# Audio.net
KiCad netlist of a schematic drawn in Altium Designer
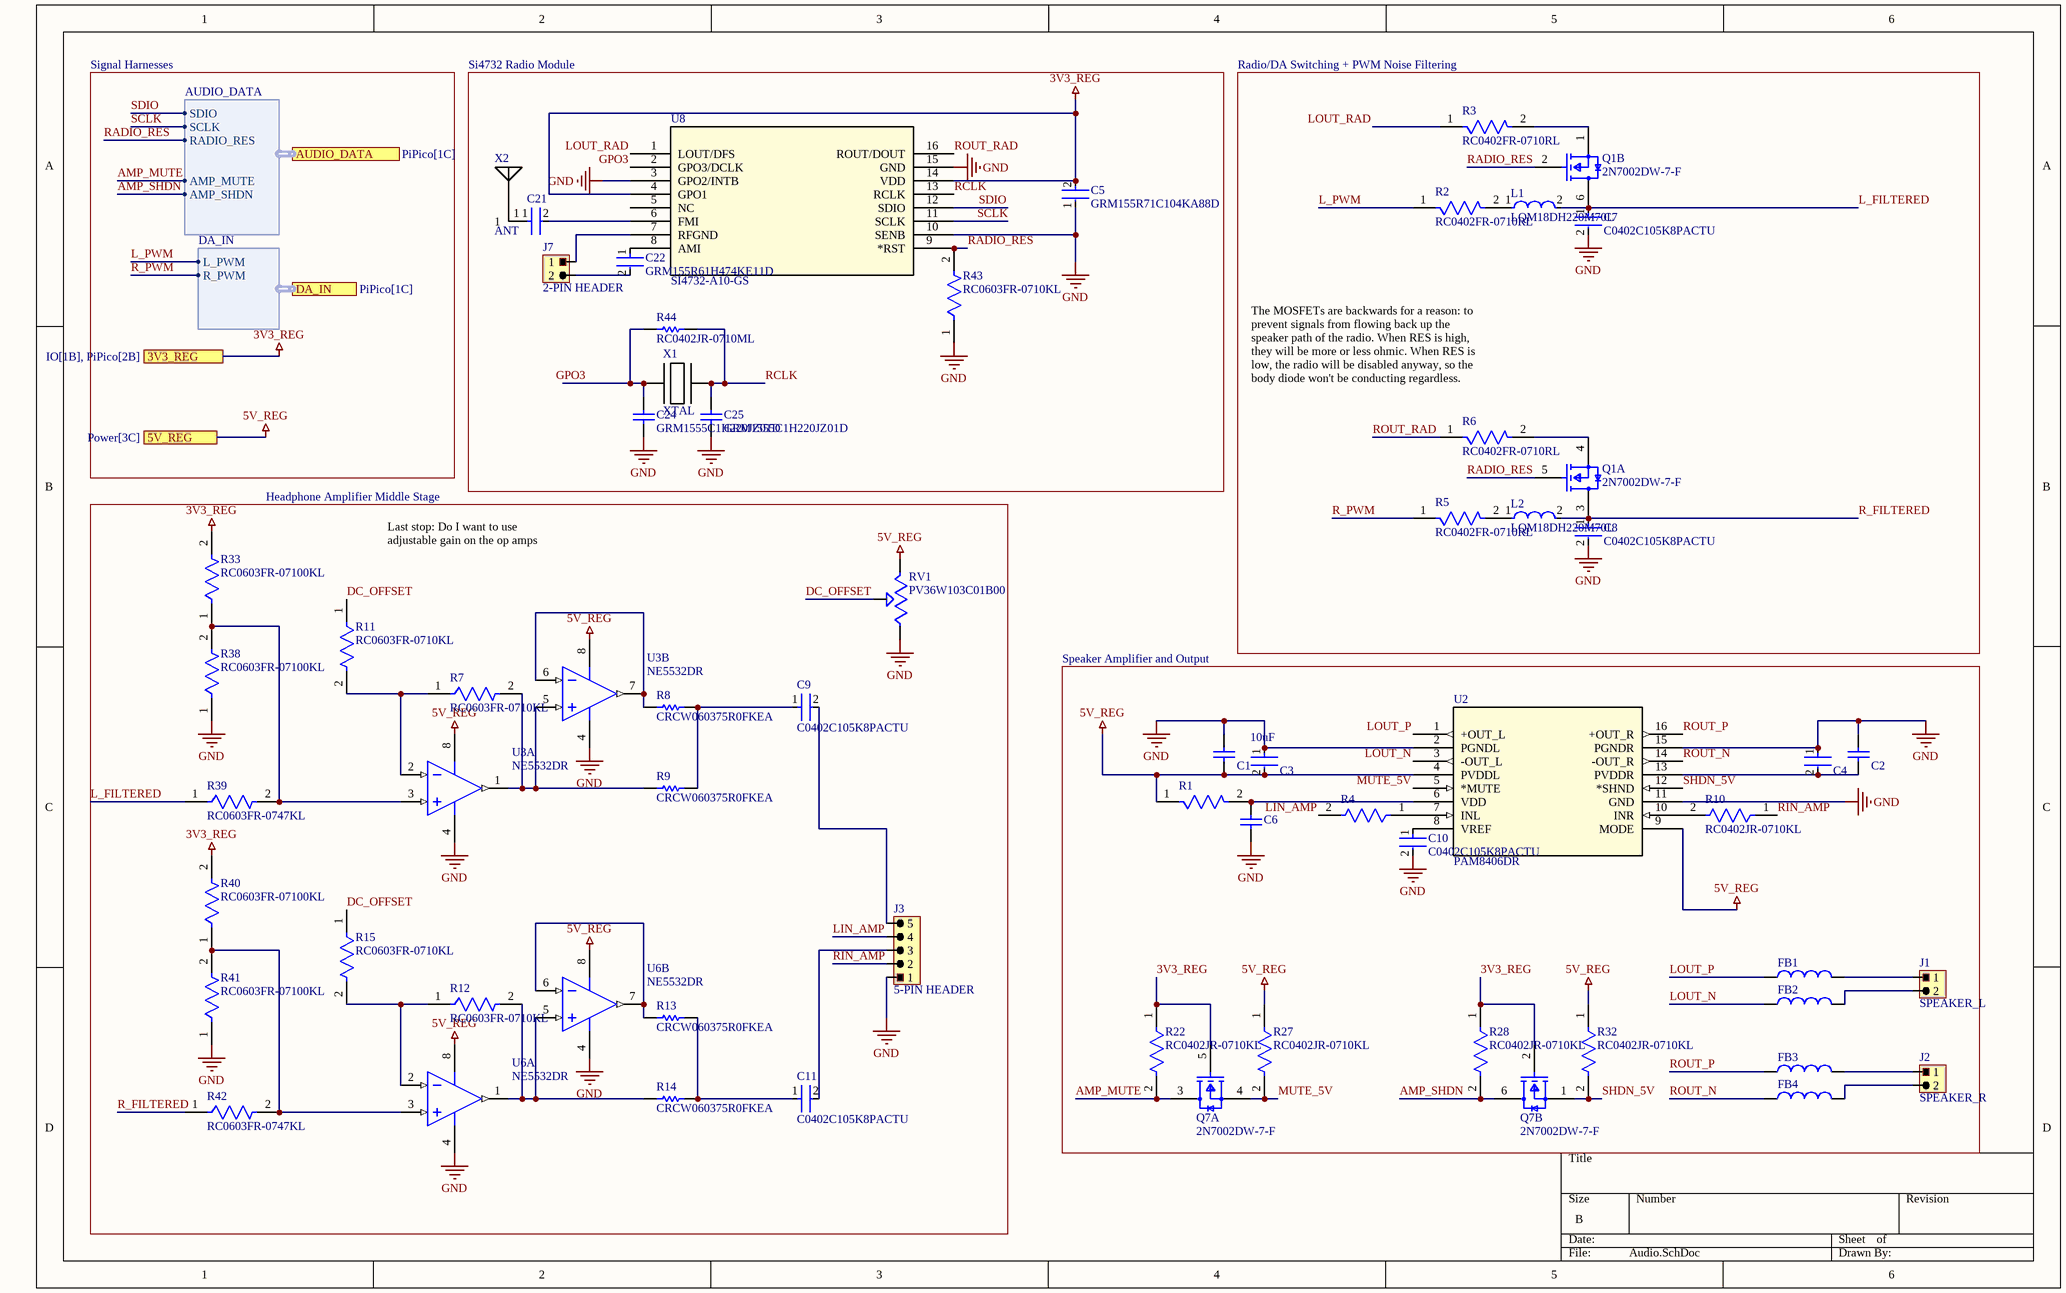
[diagram p0: Audio.SchDoc]

(export (version "E")
  (design (tool "Eeschema 10.0.6"))
  (components
    (comp (ref "C1")
      (value "C0603C105K3RACTU")
      (footprint "CAPC1608X87X35LL15T15")
      (fields (field (name "MANUFACTURER") "Kemet"))
      (libsource (lib "Altium Content Vault") (part "CAP"))
    )
    (comp (ref "C2")
      (value "C0603C105K3RACTU")
      (footprint "CAPC1608X87X35LL15T15")
      (fields (field (name "MANUFACTURER") "Kemet"))
      (libsource (lib "Altium Content Vault") (part "CAP"))
    )
    (comp (ref "C3")
      (value "C0805C106K8PACTU")
      (footprint "FP-C0805C-DG-MFG")
      (description "CAP CER 10UF 10V X5R 0805")
      (fields
        (field (name "TOLERANCE") "10%")
        (field (name "MANUFACTURER") "Kemet")
        (field (name "CAPACITANCE") "10uF")
      )
      (libsource (lib "Altium Content Vault") (part "11868f565c42a9108669ba33697ecf6"))
    )
    (comp (ref "C4")
      (value "C0805C106K8PACTU")
      (footprint "FP-C0805C-DG-MFG")
      (description "CAP CER 10UF 10V X5R 0805")
      (fields (field (name "TOLERANCE") "10%") (field (name "MANUFACTURER") "Kemet"))
      (libsource (lib "Altium Content Vault") (part "11868f565c42a9108669ba33697ecf6"))
    )
    (comp (ref "C5")
      (value "GRM155R71C104KA88D")
      (footprint "FP-GRM15-MFG")
      (description "CAP CER 0.1UF 16V X7R 0402")
      (fields
        (field (name "TOLERANCE") "10%")
        (field (name "OCTOPART") "https://octopart.com/grm155r71c104ka88d-murata-196880")
      )
      (libsource (lib "Altium Content Vault") (part "236180d848d6139a670b325ea6854c9"))
    )
    (comp (ref "C6")
      (value "C0603C105K3RACTU")
      (footprint "CAPC1608X87X35LL15T15")
      (fields (field (name "MANUFACTURER") "Kemet"))
      (libsource (lib "Altium Content Vault") (part "CAP"))
    )
    (comp (ref "C7")
      (value "C0402C105K8PACTU")
      (footprint "FP-C0402C105K8PACTU-MFG")
      (description "CAP CER 1UF 10V X5R 0402")
      (fields (field (name "VOLTAGE") "10V") (field (name "TOLERANCE") "10%"))
      (libsource (lib "Altium Content Vault") (part "11868f565c42a9108669ba33697ecf6"))
    )
    (comp (ref "C8")
      (value "C0402C105K8PACTU")
      (footprint "FP-C0402C105K8PACTU-MFG")
      (description "CAP CER 1UF 10V X5R 0402")
      (fields (field (name "VOLTAGE") "10V") (field (name "TOLERANCE") "10%"))
      (libsource (lib "Altium Content Vault") (part "11868f565c42a9108669ba33697ecf6"))
    )
    (comp (ref "C9")
      (value "C0402C105K8PACTU")
      (footprint "FP-C0402C105K8PACTU-MFG")
      (description "CAP CER 1UF 10V X5R 0402")
      (fields (field (name "VOLTAGE") "10V") (field (name "TOLERANCE") "10%"))
      (libsource (lib "Altium Content Vault") (part "11868f565c42a9108669ba33697ecf6"))
    )
    (comp (ref "C10")
      (value "C0402C105K8PACTU")
      (footprint "FP-C0402C105K8PACTU-MFG")
      (description "CAP CER 1UF 10V X5R 0402")
      (fields (field (name "VOLTAGE") "10V") (field (name "TOLERANCE") "10%"))
      (libsource (lib "Altium Content Vault") (part "11868f565c42a9108669ba33697ecf6"))
    )
    (comp (ref "C11")
      (value "C0402C105K8PACTU")
      (footprint "FP-C0402C105K8PACTU-MFG")
      (description "CAP CER 1UF 10V X5R 0402")
      (fields (field (name "VOLTAGE") "10V") (field (name "TOLERANCE") "10%"))
      (libsource (lib "Altium Content Vault") (part "11868f565c42a9108669ba33697ecf6"))
    )
    (comp (ref "C21")
      (value "GRM1555C1H102JA01D")
      (footprint "FP-GRM155-0_05-IPC_B")
      (description "Chip Multilayer Ceramic Capacitors for General Purpose, 0402, 1000pF, C0G, 30ppm/°C, 5%, 50V")
      (fields (field (name "TOLERANCE") "5%") (field (name "VOLTAGE") "50V"))
      (libsource (lib "Altium Content Vault") (part "02cd4be3c70576c341d710602a673aa"))
    )
    (comp (ref "C22")
      (value "GRM155R61H474KE11D")
      (footprint "FP-GRM155-0_1-IPC_B")
      (description "Chip Multilayer Ceramic Capacitors for General Purpose, 0402, 0.47uF, X5R, 15%, 10%, 50V")
      (fields (field (name "TOLERANCE") "10%"))
      (libsource (lib "Altium Content Vault") (part "11868f565c42a9108669ba33697ecf6"))
    )
    (comp (ref "C24")
      (value "GRM1555C1H220JZ01D")
      (footprint "CAPC1005X55X25NL05T10")
      (fields (field (name "MANUFACTURER") "Murata"))
      (libsource (lib "Altium Content Vault") (part "CAP"))
    )
    (comp (ref "C25")
      (value "GRM1555C1H220JZ01D")
      (footprint "CAPC1005X55X25NL05T10")
      (fields (field (name "MANUFACTURER") "Murata"))
      (libsource (lib "Altium Content Vault") (part "CAP"))
    )
    (comp (ref "FB1")
      (value "742792097")
      (footprint "WE-CBF_0805_L2W1.2H0.9_HC")
      (fields (field (name "TOLERANCE") "25%"))
      (libsource (lib "Altium Content Vault") (part "Ferrite"))
    )
    (comp (ref "FB2")
      (value "742792097")
      (footprint "WE-CBF_0805_L2W1.2H0.9_HC")
      (fields (field (name "TOLERANCE") "25%"))
      (libsource (lib "Altium Content Vault") (part "Ferrite"))
    )
    (comp (ref "FB3")
      (value "742792097")
      (footprint "WE-CBF_0805_L2W1.2H0.9_HC")
      (fields (field (name "TOLERANCE") "25%"))
      (libsource (lib "Altium Content Vault") (part "Ferrite"))
    )
    (comp (ref "FB4")
      (value "742792097")
      (footprint "WE-CBF_0805_L2W1.2H0.9_HC")
      (fields (field (name "TOLERANCE") "25%"))
      (libsource (lib "Altium Content Vault") (part "Ferrite"))
    )
    (comp (ref "J1")
      (value "SPEAKER_L")
      (footprint "2-pin Header (Generic)")
      (libsource (lib "") (part "2-PIN HEADER_1"))
    )
    (comp (ref "J2")
      (value "SPEAKER_R")
      (footprint "2-pin Header (Generic)")
      (libsource (lib "") (part "2-PIN HEADER_1"))
    )
    (comp (ref "J3")
      (value "5-PIN HEADER")
      (footprint "5-pin Header (Generic)")
      (libsource (lib "ECE299_PCB") (part "5-PIN HEADER"))
    )
    (comp (ref "J7")
      (value "2-PIN HEADER")
      (footprint "2-pin Header (Generic)")
      (libsource (lib "ECE299_PCB") (part "2-PIN HEADER"))
    )
    (comp (ref "L1")
      (value "LQM18DH220M70L")
      (footprint "FP-LQM18DN_70-MFG")
      (description "LQM18DH220M70L Inductor Chip Shielded Multilayer 22uH 20% 1MHz Ferrite 200mA 0603 Emboss T/R")
      (fields (field (name "TOLERANCE") "20%"))
      (libsource (lib "Altium Content Vault") (part "725321dda6339637d4d059423bc1c3c"))
    )
    (comp (ref "L2")
      (value "LQM18DH220M70L")
      (footprint "FP-LQM18DN_70-MFG")
      (description "LQM18DH220M70L Inductor Chip Shielded Multilayer 22uH 20% 1MHz Ferrite 200mA 0603 Emboss T/R")
      (fields (field (name "TOLERANCE") "20%"))
      (libsource (lib "Altium Content Vault") (part "725321dda6339637d4d059423bc1c3c"))
    )
    (comp (ref "Q1")
      (value "2N7002DW-7-F")
      (footprint "FP-SOT363-IPC_C")
      (description "MOSFET 2N-CH 60V 0.23A SOT-363")
      (libsource (lib "Altium Content Vault") (part "ecafc9d1340cdd65b0d02313e96d8fb"))
    )
    (comp (ref "Q7")
      (value "2N7002DW-7-F")
      (footprint "FP-SOT363-IPC_C")
      (description "MOSFET 2N-CH 60V 0.23A SOT-363")
      (libsource (lib "Altium Content Vault") (part "ecafc9d1340cdd65b0d02313e96d8fb"))
    )
    (comp (ref "R1")
      (value "RC0402FR-0710RL")
      (footprint "FP-RC0402-0_4-MFG")
      (fields (field (name "TOLERANCE") "1%"))
      (libsource (lib "Altium Content Vault") (part "1029c3af85768c4190bb7ad29bc67b5"))
    )
    (comp (ref "R2")
      (value "RC0402FR-0710RL")
      (footprint "FP-RC0402-0_4-MFG")
      (fields (field (name "TOLERANCE") "1%"))
      (libsource (lib "Altium Content Vault") (part "1029c3af85768c4190bb7ad29bc67b5"))
    )
    (comp (ref "R3")
      (value "RC0402FR-0710RL")
      (footprint "FP-RC0402-0_4-MFG")
      (fields (field (name "TOLERANCE") "1%"))
      (libsource (lib "Altium Content Vault") (part "1029c3af85768c4190bb7ad29bc67b5"))
    )
    (comp (ref "R4")
      (value "RC0402JR-0710KL")
      (footprint "RC0402N_YAG")
      (description "RES 10K OHM 5% 1/16W 0402")
      (fields (field (name "TOLERANCE") "5%"))
      (libsource (lib "ECE299_PCB") (part "CMP-2002-07915-3"))
    )
    (comp (ref "R5")
      (value "RC0402FR-0710RL")
      (footprint "FP-RC0402-0_4-MFG")
      (fields (field (name "TOLERANCE") "1%"))
      (libsource (lib "Altium Content Vault") (part "1029c3af85768c4190bb7ad29bc67b5"))
    )
    (comp (ref "R6")
      (value "RC0402FR-0710RL")
      (footprint "FP-RC0402-0_4-MFG")
      (fields (field (name "TOLERANCE") "1%"))
      (libsource (lib "Altium Content Vault") (part "1029c3af85768c4190bb7ad29bc67b5"))
    )
    (comp (ref "R7")
      (value "RC0603FR-0710KL")
      (footprint "FP-RC0603-0_55-IPC_C")
      (description "RES 10K OHM 1% 1/10W 0603")
      (fields (field (name "TOLERANCE") "1%"))
      (libsource (lib "Altium Content Vault") (part "1029c3af85768c4190bb7ad29bc67b5"))
    )
    (comp (ref "R8")
      (value "CRCW060375R0FKEA")
      (footprint "RESC1609X50X30LL10T20")
      (fields (field (name "MANUFACTURER") "Vishay Dale"))
      (libsource (lib "Altium Content Vault") (part "RES"))
    )
    (comp (ref "R9")
      (value "CRCW060375R0FKEA")
      (footprint "RESC1609X50X30LL10T20")
      (fields (field (name "MANUFACTURER") "Vishay Dale"))
      (libsource (lib "Altium Content Vault") (part "RES"))
    )
    (comp (ref "R10")
      (value "RC0402JR-0710KL")
      (footprint "RC0402N_YAG")
      (description "RES 10K OHM 5% 1/16W 0402")
      (fields (field (name "TOLERANCE") "5%"))
      (libsource (lib "ECE299_PCB") (part "CMP-2002-07915-3"))
    )
    (comp (ref "R11")
      (value "RC0603FR-0710KL")
      (footprint "FP-RC0603-0_55-IPC_C")
      (description "RES 10K OHM 1% 1/10W 0603")
      (fields (field (name "TOLERANCE") "1%"))
      (libsource (lib "Altium Content Vault") (part "1029c3af85768c4190bb7ad29bc67b5"))
    )
    (comp (ref "R12")
      (value "RC0603FR-0710KL")
      (footprint "FP-RC0603-0_55-IPC_C")
      (description "RES 10K OHM 1% 1/10W 0603")
      (fields (field (name "TOLERANCE") "1%"))
      (libsource (lib "Altium Content Vault") (part "1029c3af85768c4190bb7ad29bc67b5"))
    )
    (comp (ref "R13")
      (value "CRCW060375R0FKEA")
      (footprint "RESC1609X50X30LL10T20")
      (fields (field (name "MANUFACTURER") "Vishay Dale"))
      (libsource (lib "Altium Content Vault") (part "RES"))
    )
    (comp (ref "R14")
      (value "CRCW060375R0FKEA")
      (footprint "RESC1609X50X30LL10T20")
      (fields (field (name "MANUFACTURER") "Vishay Dale"))
      (libsource (lib "Altium Content Vault") (part "RES"))
    )
    (comp (ref "R15")
      (value "RC0603FR-0710KL")
      (footprint "FP-RC0603-0_55-IPC_C")
      (description "RES 10K OHM 1% 1/10W 0603")
      (fields (field (name "TOLERANCE") "1%"))
      (libsource (lib "Altium Content Vault") (part "1029c3af85768c4190bb7ad29bc67b5"))
    )
    (comp (ref "R22")
      (value "RC0402JR-0710KL")
      (footprint "RC0402N_YAG")
      (description "RES 10K OHM 5% 1/16W 0402")
      (fields (field (name "TOLERANCE") "5%"))
      (libsource (lib "ECE299_PCB") (part "CMP-2002-07915-3"))
    )
    (comp (ref "R27")
      (value "RC0402JR-0710KL")
      (footprint "RC0402N_YAG")
      (description "RES 10K OHM 5% 1/16W 0402")
      (fields (field (name "TOLERANCE") "5%"))
      (libsource (lib "ECE299_PCB") (part "CMP-2002-07915-3"))
    )
    (comp (ref "R28")
      (value "RC0402JR-0710KL")
      (footprint "RC0402N_YAG")
      (description "RES 10K OHM 5% 1/16W 0402")
      (fields (field (name "TOLERANCE") "5%"))
      (libsource (lib "ECE299_PCB") (part "CMP-2002-07915-3"))
    )
    (comp (ref "R32")
      (value "RC0402JR-0710KL")
      (footprint "RC0402N_YAG")
      (description "RES 10K OHM 5% 1/16W 0402")
      (fields (field (name "TOLERANCE") "5%"))
      (libsource (lib "ECE299_PCB") (part "CMP-2002-07915-3"))
    )
    (comp (ref "R33")
      (value "RC0603FR-07100KL")
      (footprint "FP-RC0603-0_55-MFG")
      (description "RES SMD 100K OHM 1% 1/10W 0603")
      (fields (field (name "TOLERANCE") "1%"))
      (libsource (lib "Altium Content Vault") (part "1029c3af85768c4190bb7ad29bc67b5"))
    )
    (comp (ref "R38")
      (value "RC0603FR-07100KL")
      (footprint "FP-RC0603-0_55-MFG")
      (description "RES SMD 100K OHM 1% 1/10W 0603")
      (fields (field (name "TOLERANCE") "1%"))
      (libsource (lib "Altium Content Vault") (part "1029c3af85768c4190bb7ad29bc67b5"))
    )
    (comp (ref "R39")
      (value "RC0603FR-0747KL")
      (footprint "FP-RC0603FR-0747KL-MFG")
      (description "RES SMD 47K OHM 1% 1/10W 0603")
      (fields (field (name "TOLERANCE") "1%"))
      (libsource (lib "Altium Content Vault") (part "1029c3af85768c4190bb7ad29bc67b5"))
    )
    (comp (ref "R40")
      (value "RC0603FR-07100KL")
      (footprint "FP-RC0603-0_55-MFG")
      (description "RES SMD 100K OHM 1% 1/10W 0603")
      (fields (field (name "TOLERANCE") "1%"))
      (libsource (lib "Altium Content Vault") (part "1029c3af85768c4190bb7ad29bc67b5"))
    )
    (comp (ref "R41")
      (value "RC0603FR-07100KL")
      (footprint "FP-RC0603-0_55-MFG")
      (description "RES SMD 100K OHM 1% 1/10W 0603")
      (fields (field (name "TOLERANCE") "1%"))
      (libsource (lib "Altium Content Vault") (part "1029c3af85768c4190bb7ad29bc67b5"))
    )
    (comp (ref "R42")
      (value "RC0603FR-0747KL")
      (footprint "FP-RC0603FR-0747KL-MFG")
      (description "RES SMD 47K OHM 1% 1/10W 0603")
      (fields (field (name "TOLERANCE") "1%"))
      (libsource (lib "Altium Content Vault") (part "1029c3af85768c4190bb7ad29bc67b5"))
    )
    (comp (ref "R43")
      (value "RC0603FR-0710KL")
      (footprint "FP-RC0603-0_55-IPC_C")
      (description "RES 10K OHM 1% 1/10W 0603")
      (fields (field (name "TOLERANCE") "1%"))
      (libsource (lib "Altium Content Vault") (part "1029c3af85768c4190bb7ad29bc67b5"))
    )
    (comp (ref "R44")
      (value "RC0402JR-0710ML")
      (footprint "RESC1005X40X25ML05T10")
      (fields (field (name "MANUFACTURER") "Yageo / Phycomp"))
      (libsource (lib "Altium Content Vault") (part "RES"))
    )
    (comp (ref "RV1")
      (value "PV36W103C01B00")
      (footprint "TRIM_PV36W103C01B00")
      (description "10 kOhms 0.5W, 1/2W PC Pins Through Hole Trimmer Potentiometer Cermet 25.0 Turn Top Adjustment")
      (fields (field (name "DIGIKEY_PART_NUMBER") "118-PV36W103C01B00-ND") (field (name "MF") "Bourns"))
      (libsource (lib "ECE299_PCB") (part "PV36W103C01B00"))
    )
    (comp (ref "U2")
      (value "PAM8406DR")
      (footprint "SO-16_PAM8406_DIO")
      (description "No Description Available")
      (libsource (lib "ECE299_PCB") (part "PAM8406DR"))
    )
    (comp (ref "U3")
      (value "NE5532DR")
      (footprint "D0008A_N")
      (fields (field (name "MANUFACTURER") "Texas Instruments"))
      (libsource (lib "Altium Content Vault") (part "TI-AMP-D6-2-8_D"))
    )
    (comp (ref "U6")
      (value "NE5532DR")
      (footprint "D0008A_N")
      (fields (field (name "MANUFACTURER") "Texas Instruments"))
      (libsource (lib "Altium Content Vault") (part "TI-AMP-D6-2-8_D"))
    )
    (comp (ref "U8")
      (value "SI4732-A10-GS")
      (footprint "SOIC_A10-GS_SIL")
      (description "No Description Available")
      (libsource (lib "ECE299_PCB") (part "SI4732-A10-GS"))
    )
    (comp (ref "X1")
      (value "XTAL")
      (footprint "FC-135 32.7680KA-AG0")
      (libsource (lib "ECE299_PCB") (part "FC-135 32.7680KA-AG0"))
    )
    (comp (ref "X2")
      (value "ANT")
      (footprint "FM_ANTENNA_OUT")
      (libsource (lib "ECE299_PCB") (part "FM_OUT"))
    )
  )
  (nets
    (net (code "3") (name "/AMP_MUTE") (class "Default")
      (node (ref "Q7") (pin "3") (pinfunction "D1_3") (pintype "passive"))
      (node (ref "R22") (pin "2") (pinfunction "2_2") (pintype "passive"))
    )
    (net (code "4") (name "/AMP_SHDN") (class "Default")
      (node (ref "Q7") (pin "6") (pinfunction "D2_6") (pintype "passive"))
      (node (ref "R28") (pin "2") (pinfunction "2_2") (pintype "passive"))
    )
    (net (code "5") (name "/DC_OFFSET") (class "Default")
      (node (ref "R11") (pin "1") (pinfunction "1_1") (pintype "passive"))
      (node (ref "R15") (pin "1") (pinfunction "1_1") (pintype "passive"))
      (node (ref "RV1") (pin "2") (pinfunction "2_2") (pintype "passive"))
    )
    (net (code "6") (name "/GPO3") (class "Default")
      (node (ref "C24") (pin "2") (pinfunction "2_2") (pintype "passive"))
      (node (ref "R44") (pin "1") (pinfunction "1_1") (pintype "passive"))
      (node (ref "U8") (pin "2") (pinfunction "GPO3/DCLK_2") (pintype "passive"))
      (node (ref "X1") (pin "2") (pinfunction "2_2") (pintype "passive"))
    )
    (net (code "7") (name "/LIN_AMP") (class "Default")
      (node (ref "J3") (pin "4") (pinfunction "4_4") (pintype "passive"))
      (node (ref "R4") (pin "2") (pinfunction "2_2") (pintype "passive"))
    )
    (net (code "8") (name "/LOUT_N") (class "Default")
      (node (ref "FB2") (pin "1") (pinfunction "1_1") (pintype "passive"))
      (node (ref "U2") (pin "3") (pinfunction "-OUT_L_3") (pintype "output"))
    )
    (net (code "9") (name "/LOUT_P") (class "Default")
      (node (ref "FB1") (pin "1") (pinfunction "1_1") (pintype "passive"))
      (node (ref "U2") (pin "1") (pinfunction "+OUT_L_1") (pintype "output"))
    )
    (net (code "10") (name "/LOUT_RAD") (class "Default")
      (node (ref "R3") (pin "1") (pinfunction "1_1") (pintype "passive"))
      (node (ref "U8") (pin "1") (pinfunction "LOUT/DFS_1") (pintype "passive"))
    )
    (net (code "11") (name "/L_FILTERED") (class "Default")
      (node (ref "C7") (pin "1") (pinfunction "1_1") (pintype "passive"))
      (node (ref "L1") (pin "2") (pinfunction "2_2") (pintype "passive"))
      (node (ref "Q1") (pin "6") (pinfunction "D2_6") (pintype "passive"))
      (node (ref "R39") (pin "1") (pinfunction "1_1") (pintype "passive"))
    )
    (net (code "12") (name "/L_PWM") (class "Default")
      (node (ref "R2") (pin "1") (pinfunction "1_1") (pintype "passive"))
    )
    (net (code "13") (name "/MUTE_5V") (class "Default")
      (node (ref "Q7") (pin "4") (pinfunction "S1_4") (pintype "passive"))
      (node (ref "R27") (pin "2") (pinfunction "2_2") (pintype "passive"))
      (node (ref "U2") (pin "5") (pinfunction "*MUTE_5") (pintype "input"))
    )
    (net (code "14") (name "/RADIO_RES") (class "Default")
      (node (ref "Q1") (pin "2") (pinfunction "G2_2") (pintype "passive"))
      (node (ref "Q1") (pin "5") (pinfunction "G1_5") (pintype "passive"))
      (node (ref "R43") (pin "2") (pinfunction "2_2") (pintype "passive"))
      (node (ref "U8") (pin "9") (pinfunction "*RST_9") (pintype "passive"))
    )
    (net (code "15") (name "/RCLK") (class "Default")
      (node (ref "C25") (pin "2") (pinfunction "2_2") (pintype "passive"))
      (node (ref "R44") (pin "2") (pinfunction "2_2") (pintype "passive"))
      (node (ref "U8") (pin "13") (pinfunction "RCLK_13") (pintype "passive"))
      (node (ref "X1") (pin "1") (pinfunction "1_1") (pintype "passive"))
    )
    (net (code "16") (name "/RIN_AMP") (class "Default")
      (node (ref "J3") (pin "2") (pinfunction "2_2") (pintype "passive"))
      (node (ref "R10") (pin "1") (pinfunction "1_1") (pintype "passive"))
    )
    (net (code "17") (name "/ROUT_N") (class "Default")
      (node (ref "FB4") (pin "1") (pinfunction "1_1") (pintype "passive"))
      (node (ref "U2") (pin "14") (pinfunction "-OUT_R_14") (pintype "output"))
    )
    (net (code "18") (name "/ROUT_P") (class "Default")
      (node (ref "FB3") (pin "1") (pinfunction "1_1") (pintype "passive"))
      (node (ref "U2") (pin "16") (pinfunction "+OUT_R_16") (pintype "output"))
    )
    (net (code "19") (name "/ROUT_RAD") (class "Default")
      (node (ref "R6") (pin "1") (pinfunction "1_1") (pintype "passive"))
      (node (ref "U8") (pin "16") (pinfunction "ROUT/DOUT_16") (pintype "passive"))
    )
    (net (code "20") (name "/R_FILTERED") (class "Default")
      (node (ref "C8") (pin "1") (pinfunction "1_1") (pintype "passive"))
      (node (ref "L2") (pin "2") (pinfunction "2_2") (pintype "passive"))
      (node (ref "Q1") (pin "3") (pinfunction "D1_3") (pintype "passive"))
      (node (ref "R42") (pin "1") (pinfunction "1_1") (pintype "passive"))
    )
    (net (code "21") (name "/R_PWM") (class "Default")
      (node (ref "R5") (pin "1") (pinfunction "1_1") (pintype "passive"))
    )
    (net (code "22") (name "/SCLK") (class "Default")
      (node (ref "U8") (pin "11") (pinfunction "SCLK_11") (pintype "passive"))
    )
    (net (code "23") (name "/SDIO") (class "Default")
      (node (ref "U8") (pin "12") (pinfunction "SDIO_12") (pintype "passive"))
    )
    (net (code "24") (name "/SHDN_5V") (class "Default")
      (node (ref "Q7") (pin "1") (pinfunction "S2_1") (pintype "passive"))
      (node (ref "R32") (pin "2") (pinfunction "2_2") (pintype "passive"))
      (node (ref "U2") (pin "12") (pinfunction "*SHND_12") (pintype "input"))
    )
    (net (code "27") (name "3V3_REG") (class "Default")
      (node (ref "C5") (pin "2") (pinfunction "2_2") (pintype "passive"))
      (node (ref "Q7") (pin "2") (pinfunction "G2_2") (pintype "passive"))
      (node (ref "Q7") (pin "5") (pinfunction "G1_5") (pintype "passive"))
      (node (ref "R22") (pin "1") (pinfunction "1_1") (pintype "passive"))
      (node (ref "R28") (pin "1") (pinfunction "1_1") (pintype "passive"))
      (node (ref "R33") (pin "2") (pinfunction "2_2") (pintype "passive"))
      (node (ref "R40") (pin "2") (pinfunction "2_2") (pintype "passive"))
      (node (ref "U8") (pin "14") (pinfunction "VDD_14") (pintype "power_in"))
      (node (ref "U8") (pin "4") (pinfunction "GPO1_4") (pintype "passive"))
    )
    (net (code "28") (name "5V_REG") (class "Default")
      (node (ref "C1") (pin "1") (pinfunction "1_1") (pintype "passive"))
      (node (ref "C3") (pin "2") (pinfunction "2_2") (pintype "passive"))
      (node (ref "R1") (pin "1") (pinfunction "1_1") (pintype "passive"))
      (node (ref "R27") (pin "1") (pinfunction "1_1") (pintype "passive"))
      (node (ref "R32") (pin "1") (pinfunction "1_1") (pintype "passive"))
      (node (ref "RV1") (pin "3") (pinfunction "3_3") (pintype "passive"))
      (node (ref "U2") (pin "4") (pinfunction "PVDDL_4") (pintype "power_in"))
      (node (ref "U2") (pin "9") (pinfunction "MODE_9") (pintype "passive"))
      (node (ref "U3") (pin "8") (pinfunction "VCC+_8") (pintype "power_in"))
      (node (ref "U6") (pin "8") (pinfunction "VCC+_8") (pintype "power_in"))
    )
    (net (code "29") (name "GND") (class "Default")
      (node (ref "C1") (pin "2") (pinfunction "2_2") (pintype "passive"))
      (node (ref "C10") (pin "2") (pinfunction "2_2") (pintype "passive"))
      (node (ref "C2") (pin "2") (pinfunction "2_2") (pintype "passive"))
      (node (ref "C24") (pin "1") (pinfunction "1_1") (pintype "passive"))
      (node (ref "C25") (pin "1") (pinfunction "1_1") (pintype "passive"))
      (node (ref "C3") (pin "1") (pinfunction "1_1") (pintype "passive"))
      (node (ref "C4") (pin "1") (pinfunction "1_1") (pintype "passive"))
      (node (ref "C5") (pin "1") (pinfunction "1_1") (pintype "passive"))
      (node (ref "C6") (pin "1") (pinfunction "1_1") (pintype "passive"))
      (node (ref "C7") (pin "2") (pinfunction "2_2") (pintype "passive"))
      (node (ref "C8") (pin "2") (pinfunction "2_2") (pintype "passive"))
      (node (ref "J3") (pin "1") (pinfunction "1_1") (pintype "passive"))
      (node (ref "R38") (pin "1") (pinfunction "1_1") (pintype "passive"))
      (node (ref "R41") (pin "1") (pinfunction "1_1") (pintype "passive"))
      (node (ref "R43") (pin "1") (pinfunction "1_1") (pintype "passive"))
      (node (ref "RV1") (pin "1") (pinfunction "1_1") (pintype "passive"))
      (node (ref "U2") (pin "11") (pinfunction "GND_11") (pintype "power_in"))
      (node (ref "U2") (pin "15") (pinfunction "PGNDR_15") (pintype "power_in"))
      (node (ref "U2") (pin "2") (pinfunction "PGNDL_2") (pintype "power_in"))
      (node (ref "U3") (pin "4") (pinfunction "VCC-_4") (pintype "power_in"))
      (node (ref "U6") (pin "4") (pinfunction "VCC-_4") (pintype "power_in"))
      (node (ref "U8") (pin "10") (pinfunction "SENB_10") (pintype "passive"))
      (node (ref "U8") (pin "15") (pinfunction "GND_15") (pintype "power_in"))
      (node (ref "U8") (pin "3") (pinfunction "GPO2/INTB_3") (pintype "passive"))
    )
    (net (code "30") (name "Net-(C9-Pad1)") (class "Default")
      (node (ref "C9") (pin "1") (pinfunction "1_1") (pintype "passive"))
      (node (ref "R8") (pin "2") (pinfunction "2_2") (pintype "passive"))
      (node (ref "R9") (pin "2") (pinfunction "2_2") (pintype "passive"))
    )
    (net (code "31") (name "Net-(C9-Pad2)") (class "Default")
      (node (ref "C9") (pin "2") (pinfunction "2_2") (pintype "passive"))
      (node (ref "J3") (pin "5") (pinfunction "5_5") (pintype "passive"))
    )
    (net (code "32") (name "Net-(C11-Pad1)") (class "Default")
      (node (ref "C11") (pin "1") (pinfunction "1_1") (pintype "passive"))
      (node (ref "R13") (pin "2") (pinfunction "2_2") (pintype "passive"))
      (node (ref "R14") (pin "2") (pinfunction "2_2") (pintype "passive"))
    )
    (net (code "33") (name "Net-(C11-Pad2)") (class "Default")
      (node (ref "C11") (pin "2") (pinfunction "2_2") (pintype "passive"))
      (node (ref "J3") (pin "3") (pinfunction "3_3") (pintype "passive"))
    )
    (net (code "34") (name "Net-(C21-Pad1)") (class "Default")
      (node (ref "C21") (pin "1") (pinfunction "1_1") (pintype "passive"))
      (node (ref "X2") (pin "1") (pinfunction "1_1") (pintype "passive"))
    )
    (net (code "35") (name "Net-(C22-Pad2)") (class "Default")
      (node (ref "C22") (pin "2") (pinfunction "2_2") (pintype "passive"))
      (node (ref "J7") (pin "2") (pinfunction "2_2") (pintype "passive"))
    )
    (net (code "36") (name "Net-(FB1-Pad2)") (class "Default")
      (node (ref "FB1") (pin "2") (pinfunction "2_2") (pintype "passive"))
      (node (ref "J1") (pin "1") (pinfunction "1_1") (pintype "passive"))
    )
    (net (code "37") (name "Net-(FB2-Pad2)") (class "Default")
      (node (ref "FB2") (pin "2") (pinfunction "2_2") (pintype "passive"))
      (node (ref "J1") (pin "2") (pinfunction "2_2") (pintype "passive"))
    )
    (net (code "38") (name "Net-(FB3-Pad2)") (class "Default")
      (node (ref "FB3") (pin "2") (pinfunction "2_2") (pintype "passive"))
      (node (ref "J2") (pin "1") (pinfunction "1_1") (pintype "passive"))
    )
    (net (code "39") (name "Net-(FB4-Pad2)") (class "Default")
      (node (ref "FB4") (pin "2") (pinfunction "2_2") (pintype "passive"))
      (node (ref "J2") (pin "2") (pinfunction "2_2") (pintype "passive"))
    )
    (net (code "40") (name "Net-(L1-Pad1)") (class "Default")
      (node (ref "L1") (pin "1") (pinfunction "1_1") (pintype "passive"))
      (node (ref "R2") (pin "2") (pinfunction "2_2") (pintype "passive"))
    )
    (net (code "41") (name "Net-(L2-Pad1)") (class "Default")
      (node (ref "L2") (pin "1") (pinfunction "1_1") (pintype "passive"))
      (node (ref "R5") (pin "2") (pinfunction "2_2") (pintype "passive"))
    )
    (net (code "42") (name "Net-(Q1A-S1)") (class "Default")
      (node (ref "Q1") (pin "4") (pinfunction "S1_4") (pintype "passive"))
      (node (ref "R6") (pin "2") (pinfunction "2_2") (pintype "passive"))
    )
    (net (code "43") (name "Net-(Q1B-S2)") (class "Default")
      (node (ref "Q1") (pin "1") (pinfunction "S2_1") (pintype "passive"))
      (node (ref "R3") (pin "2") (pinfunction "2_2") (pintype "passive"))
    )
    (net (code "44") (name "Net-(U2-INL)") (class "Default")
      (node (ref "R4") (pin "1") (pinfunction "1_1") (pintype "passive"))
      (node (ref "U2") (pin "7") (pinfunction "INL_7") (pintype "input"))
    )
    (net (code "45") (name "Net-(U2-INR)") (class "Default")
      (node (ref "R10") (pin "2") (pinfunction "2_2") (pintype "passive"))
      (node (ref "U2") (pin "10") (pinfunction "INR_10") (pintype "input"))
    )
    (net (code "46") (name "Net-(U2-PVDDR)") (class "Default")
      (node (ref "C2") (pin "1") (pinfunction "1_1") (pintype "passive"))
      (node (ref "C4") (pin "2") (pinfunction "2_2") (pintype "passive"))
      (node (ref "U2") (pin "13") (pinfunction "PVDDR_13") (pintype "power_in"))
    )
    (net (code "47") (name "Net-(U2-VDD)") (class "Default")
      (node (ref "C6") (pin "2") (pinfunction "2_2") (pintype "passive"))
      (node (ref "R1") (pin "2") (pinfunction "2_2") (pintype "passive"))
      (node (ref "U2") (pin "6") (pinfunction "VDD_6") (pintype "power_in"))
    )
    (net (code "48") (name "Net-(U2-VREF)") (class "Default")
      (node (ref "C10") (pin "1") (pinfunction "1_1") (pintype "passive"))
      (node (ref "U2") (pin "8") (pinfunction "VREF_8") (pintype "power_in"))
    )
    (net (code "49") (name "Net-(U3A-IN1+)") (class "Default")
      (node (ref "R33") (pin "1") (pinfunction "1_1") (pintype "passive"))
      (node (ref "R38") (pin "2") (pinfunction "2_2") (pintype "passive"))
      (node (ref "R39") (pin "2") (pinfunction "2_2") (pintype "passive"))
      (node (ref "U3") (pin "3") (pinfunction "IN1+_3") (pintype "input"))
    )
    (net (code "50") (name "Net-(U3A-IN1-)") (class "Default")
      (node (ref "R11") (pin "2") (pinfunction "2_2") (pintype "passive"))
      (node (ref "R7") (pin "1") (pinfunction "1_1") (pintype "passive"))
      (node (ref "U3") (pin "2") (pinfunction "IN1-_2") (pintype "input"))
    )
    (net (code "51") (name "Net-(U3A-OUT1)") (class "Default")
      (node (ref "R7") (pin "2") (pinfunction "2_2") (pintype "passive"))
      (node (ref "R9") (pin "1") (pinfunction "1_1") (pintype "passive"))
      (node (ref "U3") (pin "1") (pinfunction "OUT1_1") (pintype "output"))
      (node (ref "U3") (pin "5") (pinfunction "IN2+_5") (pintype "input"))
    )
    (net (code "52") (name "Net-(U3B-IN2-)") (class "Default")
      (node (ref "R8") (pin "1") (pinfunction "1_1") (pintype "passive"))
      (node (ref "U3") (pin "6") (pinfunction "IN2-_6") (pintype "input"))
      (node (ref "U3") (pin "7") (pinfunction "OUT2_7") (pintype "output"))
    )
    (net (code "53") (name "Net-(U6A-IN1+)") (class "Default")
      (node (ref "R40") (pin "1") (pinfunction "1_1") (pintype "passive"))
      (node (ref "R41") (pin "2") (pinfunction "2_2") (pintype "passive"))
      (node (ref "R42") (pin "2") (pinfunction "2_2") (pintype "passive"))
      (node (ref "U6") (pin "3") (pinfunction "IN1+_3") (pintype "input"))
    )
    (net (code "54") (name "Net-(U6A-IN1-)") (class "Default")
      (node (ref "R12") (pin "1") (pinfunction "1_1") (pintype "passive"))
      (node (ref "R15") (pin "2") (pinfunction "2_2") (pintype "passive"))
      (node (ref "U6") (pin "2") (pinfunction "IN1-_2") (pintype "input"))
    )
    (net (code "55") (name "Net-(U6A-OUT1)") (class "Default")
      (node (ref "R12") (pin "2") (pinfunction "2_2") (pintype "passive"))
      (node (ref "R14") (pin "1") (pinfunction "1_1") (pintype "passive"))
      (node (ref "U6") (pin "1") (pinfunction "OUT1_1") (pintype "output"))
      (node (ref "U6") (pin "5") (pinfunction "IN2+_5") (pintype "input"))
    )
    (net (code "56") (name "Net-(U6B-IN2-)") (class "Default")
      (node (ref "R13") (pin "1") (pinfunction "1_1") (pintype "passive"))
      (node (ref "U6") (pin "6") (pinfunction "IN2-_6") (pintype "input"))
      (node (ref "U6") (pin "7") (pinfunction "OUT2_7") (pintype "output"))
    )
    (net (code "57") (name "Net-(U8-AMI)") (class "Default")
      (node (ref "C22") (pin "1") (pinfunction "1_1") (pintype "passive"))
      (node (ref "U8") (pin "8") (pinfunction "AMI_8") (pintype "passive"))
    )
    (net (code "58") (name "Net-(U8-FMI)") (class "Default")
      (node (ref "C21") (pin "2") (pinfunction "2_2") (pintype "passive"))
      (node (ref "U8") (pin "6") (pinfunction "FMI_6") (pintype "passive"))
    )
    (net (code "59") (name "Net-(U8-RFGND)") (class "Default")
      (node (ref "J7") (pin "1") (pinfunction "1_1") (pintype "passive"))
      (node (ref "U8") (pin "7") (pinfunction "RFGND_7") (pintype "power_in"))
    )
    (net (code "60") (name "unconnected-(U8-NC-Pad5)") (class "Default")
      (node (ref "U8") (pin "5") (pinfunction "NC_5") (pintype "passive"))
    )
  )
)
